# 10w_CREE_LED_driver.net
KiCad netlist of a schematic drawn in EAGLE
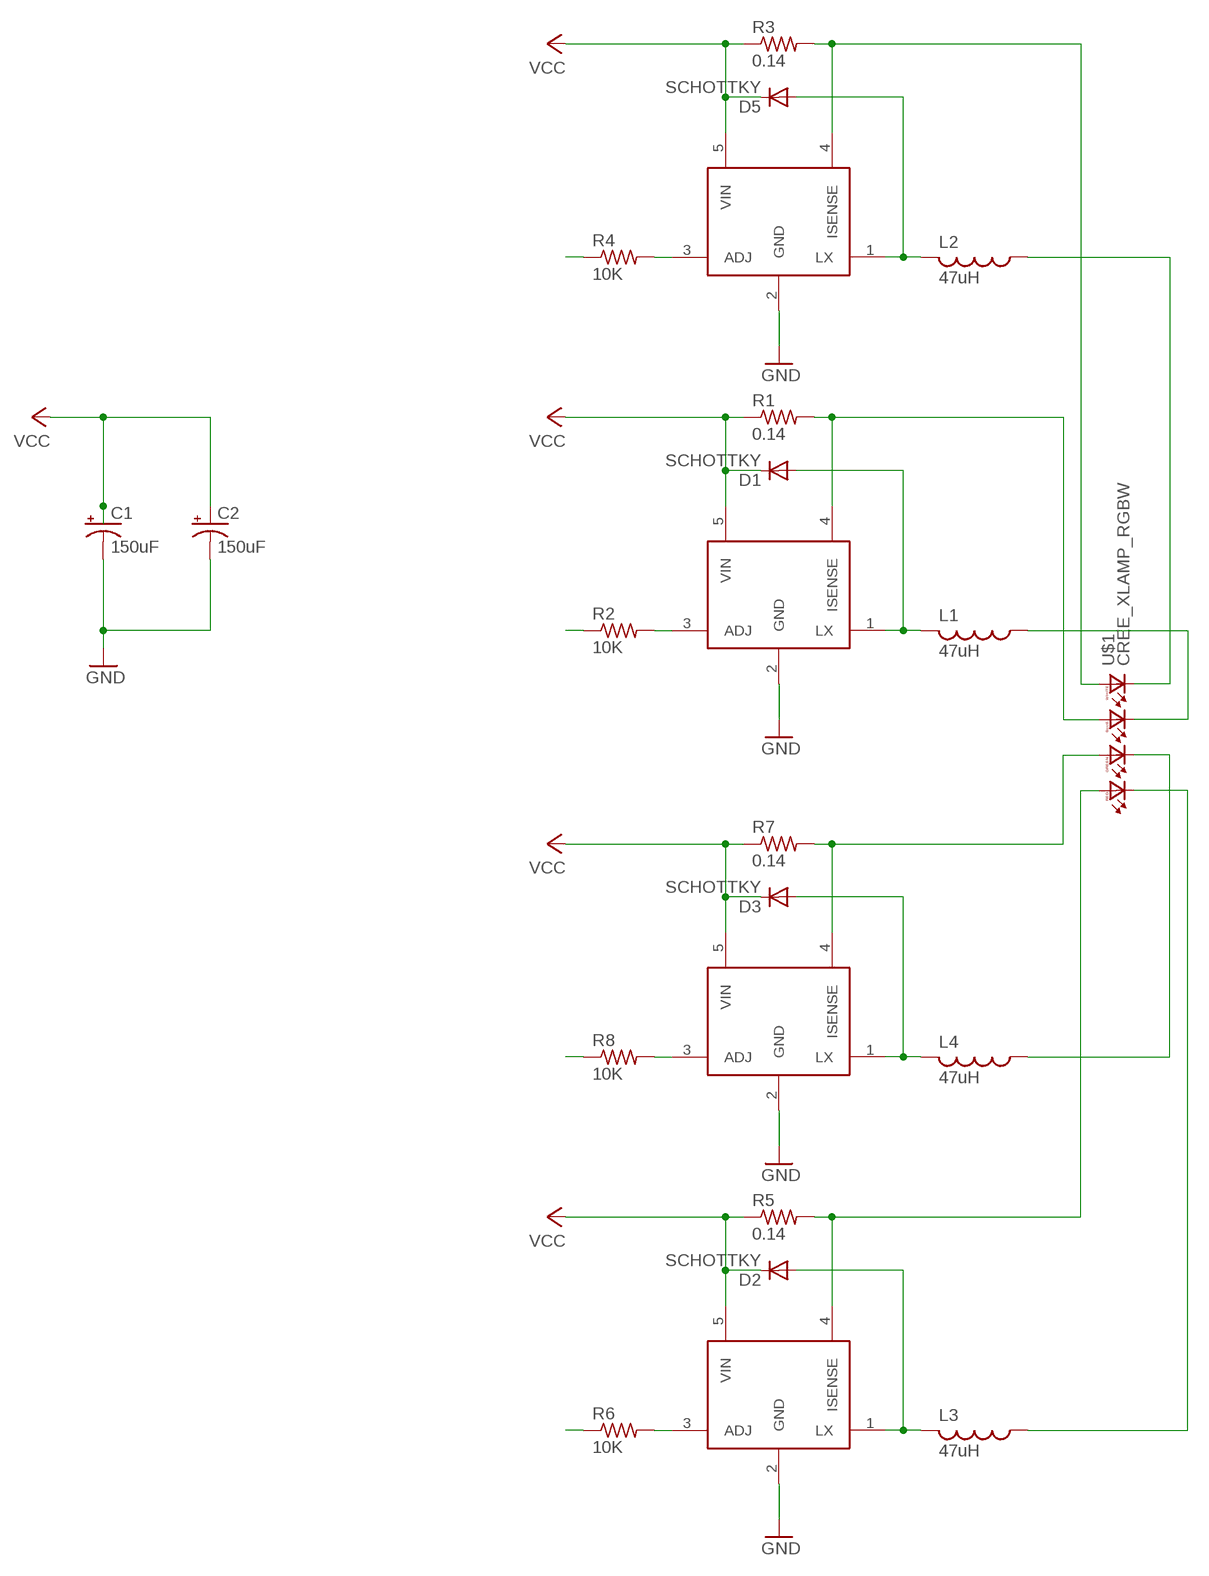
[diagram p0: schematic, sheet 1]

(export (version "E")
  (design (tool "Eeschema 10.0.6"))
  (components
    (comp (ref "C1")
      (value "150uF")
      (footprint "eagle-import:175TMP-0810")
      (libsource (lib "eagle-import") (part "CPOL-US175TMP-0810"))
    )
    (comp (ref "C2")
      (value "150uF")
      (footprint "eagle-import:175TMP-0810")
      (libsource (lib "eagle-import") (part "CPOL-US175TMP-0810"))
    )
    (comp (ref "D1")
      (value "SCHOTTKY")
      (footprint "eagle-import:DO214AC")
      (libsource (lib "eagle-import") (part "DIODE-DO214AC"))
    )
    (comp (ref "D2")
      (value "SCHOTTKY")
      (footprint "eagle-import:DO214AC")
      (libsource (lib "eagle-import") (part "DIODE-DO214AC"))
    )
    (comp (ref "D3")
      (value "SCHOTTKY")
      (footprint "eagle-import:DO214AC")
      (libsource (lib "eagle-import") (part "DIODE-DO214AC"))
    )
    (comp (ref "D5")
      (value "SCHOTTKY")
      (footprint "eagle-import:DO214AC")
      (libsource (lib "eagle-import") (part "DIODE-DO214AC"))
    )
    (comp (ref "L1")
      (value "47uH")
      (footprint "eagle-import:TDK6045")
      (libsource (lib "eagle-import") (part "L-US"))
    )
    (comp (ref "L2")
      (value "47uH")
      (footprint "eagle-import:TDK6045")
      (libsource (lib "eagle-import") (part "L-US"))
    )
    (comp (ref "L3")
      (value "47uH")
      (footprint "eagle-import:TDK6045")
      (libsource (lib "eagle-import") (part "L-US"))
    )
    (comp (ref "L4")
      (value "47uH")
      (footprint "eagle-import:TDK6045")
      (libsource (lib "eagle-import") (part "L-US"))
    )
    (comp (ref "R1")
      (value "0.14")
      (footprint "eagle-import:R0805")
      (libsource (lib "eagle-import") (part "R-US_R0805"))
    )
    (comp (ref "R2")
      (value "10K")
      (footprint "eagle-import:R0603")
      (libsource (lib "eagle-import") (part "R-US_R0603"))
    )
    (comp (ref "R3")
      (value "0.14")
      (footprint "eagle-import:R0805")
      (libsource (lib "eagle-import") (part "R-US_R0805"))
    )
    (comp (ref "R4")
      (value "10K")
      (footprint "eagle-import:R0603")
      (libsource (lib "eagle-import") (part "R-US_R0603"))
    )
    (comp (ref "R5")
      (value "0.14")
      (footprint "eagle-import:R0805")
      (libsource (lib "eagle-import") (part "R-US_R0805"))
    )
    (comp (ref "R6")
      (value "10K")
      (footprint "eagle-import:R0603")
      (libsource (lib "eagle-import") (part "R-US_R0603"))
    )
    (comp (ref "R7")
      (value "0.14")
      (footprint "eagle-import:R0805")
      (libsource (lib "eagle-import") (part "R-US_R0805"))
    )
    (comp (ref "R8")
      (value "10K")
      (footprint "eagle-import:R0603")
      (libsource (lib "eagle-import") (part "R-US_R0603"))
    )
    (comp (ref "U$1")
      (value "CREE_XLAMP_RGBW")
      (footprint "eagle-import:CREE_XLAMP_XML")
      (libsource (lib "eagle-import") (part "CREE_XLAMP_RGBW"))
    )
    (comp (ref "U$2")
      (value "ZLED7000-LEDDRIVER")
      (footprint "eagle-import:SOT89-5")
      (libsource (lib "eagle-import") (part "ZLED7000-LEDDRIVER"))
    )
    (comp (ref "U$3")
      (value "ZLED7000-LEDDRIVER")
      (footprint "eagle-import:SOT89-5")
      (libsource (lib "eagle-import") (part "ZLED7000-LEDDRIVER"))
    )
    (comp (ref "U$4")
      (value "ZLED7000-LEDDRIVER")
      (footprint "eagle-import:SOT89-5")
      (libsource (lib "eagle-import") (part "ZLED7000-LEDDRIVER"))
    )
    (comp (ref "U$6")
      (value "ZLED7000-LEDDRIVER")
      (footprint "eagle-import:SOT89-5")
      (libsource (lib "eagle-import") (part "ZLED7000-LEDDRIVER"))
    )
  )
  (nets
    (net (code "1") (name "GND") (class "Default")
      (node (ref "C1") (pin "-") (pinfunction "-_-") (pintype "passive"))
      (node (ref "C2") (pin "-") (pinfunction "-_-") (pintype "passive"))
      (node (ref "U$2") (pin "2") (pinfunction "GND_2") (pintype "bidirectional"))
      (node (ref "U$3") (pin "2") (pinfunction "GND_2") (pintype "bidirectional"))
      (node (ref "U$4") (pin "2") (pinfunction "GND_2") (pintype "bidirectional"))
      (node (ref "U$6") (pin "2") (pinfunction "GND_2") (pintype "bidirectional"))
    )
    (net (code "2") (name "Net-(U$1-BA)") (class "Default")
      (node (ref "R1") (pin "2") (pinfunction "2_2") (pintype "passive"))
      (node (ref "U$1") (pin "3") (pinfunction "BA_3") (pintype "passive"))
      (node (ref "U$2") (pin "4") (pinfunction "ISENSE_4") (pintype "bidirectional"))
    )
    (net (code "3") (name "Net-(U$1-BC)") (class "Default")
      (node (ref "L1") (pin "1") (pinfunction "1_1") (pintype "passive"))
      (node (ref "U$1") (pin "6") (pinfunction "BC_6") (pintype "passive"))
    )
    (net (code "4") (name "Net-(U$1-GA)") (class "Default")
      (node (ref "R7") (pin "2") (pinfunction "2_2") (pintype "passive"))
      (node (ref "U$1") (pin "2") (pinfunction "GA_2") (pintype "passive"))
      (node (ref "U$4") (pin "4") (pinfunction "ISENSE_4") (pintype "bidirectional"))
    )
    (net (code "5") (name "Net-(U$1-GC)") (class "Default")
      (node (ref "L4") (pin "1") (pinfunction "1_1") (pintype "passive"))
      (node (ref "U$1") (pin "7") (pinfunction "GC_7") (pintype "passive"))
    )
    (net (code "6") (name "Net-(U$1-RA)") (class "Default")
      (node (ref "R5") (pin "2") (pinfunction "2_2") (pintype "passive"))
      (node (ref "U$1") (pin "1") (pinfunction "RA_1") (pintype "passive"))
      (node (ref "U$3") (pin "4") (pinfunction "ISENSE_4") (pintype "bidirectional"))
    )
    (net (code "7") (name "Net-(U$1-RC)") (class "Default")
      (node (ref "L3") (pin "1") (pinfunction "1_1") (pintype "passive"))
      (node (ref "U$1") (pin "8") (pinfunction "RC_8") (pintype "passive"))
    )
    (net (code "8") (name "Net-(U$1-WA)") (class "Default")
      (node (ref "R3") (pin "2") (pinfunction "2_2") (pintype "passive"))
      (node (ref "U$1") (pin "4") (pinfunction "WA_4") (pintype "passive"))
      (node (ref "U$6") (pin "4") (pinfunction "ISENSE_4") (pintype "bidirectional"))
    )
    (net (code "9") (name "Net-(U$1-WC)") (class "Default")
      (node (ref "L2") (pin "1") (pinfunction "1_1") (pintype "passive"))
      (node (ref "U$1") (pin "5") (pinfunction "WC_5") (pintype "passive"))
    )
    (net (code "10") (name "Net-(U$2-ADJ)") (class "Default")
      (node (ref "R2") (pin "2") (pinfunction "2_2") (pintype "passive"))
      (node (ref "U$2") (pin "3") (pinfunction "ADJ_3") (pintype "bidirectional"))
    )
    (net (code "11") (name "Net-(U$2-LX)") (class "Default")
      (node (ref "D1") (pin "A") (pinfunction "A_A") (pintype "passive"))
      (node (ref "L1") (pin "2") (pinfunction "2_2") (pintype "passive"))
      (node (ref "U$2") (pin "1") (pinfunction "LX_1") (pintype "bidirectional"))
    )
    (net (code "12") (name "Net-(U$3-ADJ)") (class "Default")
      (node (ref "R6") (pin "2") (pinfunction "2_2") (pintype "passive"))
      (node (ref "U$3") (pin "3") (pinfunction "ADJ_3") (pintype "bidirectional"))
    )
    (net (code "13") (name "Net-(U$3-LX)") (class "Default")
      (node (ref "D2") (pin "A") (pinfunction "A_A") (pintype "passive"))
      (node (ref "L3") (pin "2") (pinfunction "2_2") (pintype "passive"))
      (node (ref "U$3") (pin "1") (pinfunction "LX_1") (pintype "bidirectional"))
    )
    (net (code "14") (name "Net-(U$4-ADJ)") (class "Default")
      (node (ref "R8") (pin "2") (pinfunction "2_2") (pintype "passive"))
      (node (ref "U$4") (pin "3") (pinfunction "ADJ_3") (pintype "bidirectional"))
    )
    (net (code "15") (name "Net-(U$4-LX)") (class "Default")
      (node (ref "D3") (pin "A") (pinfunction "A_A") (pintype "passive"))
      (node (ref "L4") (pin "2") (pinfunction "2_2") (pintype "passive"))
      (node (ref "U$4") (pin "1") (pinfunction "LX_1") (pintype "bidirectional"))
    )
    (net (code "16") (name "Net-(U$6-ADJ)") (class "Default")
      (node (ref "R4") (pin "2") (pinfunction "2_2") (pintype "passive"))
      (node (ref "U$6") (pin "3") (pinfunction "ADJ_3") (pintype "bidirectional"))
    )
    (net (code "17") (name "Net-(U$6-LX)") (class "Default")
      (node (ref "D5") (pin "A") (pinfunction "A_A") (pintype "passive"))
      (node (ref "L2") (pin "2") (pinfunction "2_2") (pintype "passive"))
      (node (ref "U$6") (pin "1") (pinfunction "LX_1") (pintype "bidirectional"))
    )
    (net (code "18") (name "VCC") (class "Default")
      (node (ref "C1") (pin "+") (pinfunction "+_+") (pintype "passive"))
      (node (ref "C2") (pin "+") (pinfunction "+_+") (pintype "passive"))
      (node (ref "D1") (pin "C") (pinfunction "C_C") (pintype "passive"))
      (node (ref "D2") (pin "C") (pinfunction "C_C") (pintype "passive"))
      (node (ref "D3") (pin "C") (pinfunction "C_C") (pintype "passive"))
      (node (ref "D5") (pin "C") (pinfunction "C_C") (pintype "passive"))
      (node (ref "R1") (pin "1") (pinfunction "1_1") (pintype "passive"))
      (node (ref "R3") (pin "1") (pinfunction "1_1") (pintype "passive"))
      (node (ref "R5") (pin "1") (pinfunction "1_1") (pintype "passive"))
      (node (ref "R7") (pin "1") (pinfunction "1_1") (pintype "passive"))
      (node (ref "U$2") (pin "5") (pinfunction "VIN_5") (pintype "bidirectional"))
      (node (ref "U$3") (pin "5") (pinfunction "VIN_5") (pintype "bidirectional"))
      (node (ref "U$4") (pin "5") (pinfunction "VIN_5") (pintype "bidirectional"))
      (node (ref "U$6") (pin "5") (pinfunction "VIN_5") (pintype "bidirectional"))
    )
    (net (code "19") (name "unconnected-(R2-Pad1)") (class "Default")
      (node (ref "R2") (pin "1") (pinfunction "1_1") (pintype "passive"))
    )
    (net (code "20") (name "unconnected-(R4-Pad1)") (class "Default")
      (node (ref "R4") (pin "1") (pinfunction "1_1") (pintype "passive"))
    )
    (net (code "21") (name "unconnected-(R6-Pad1)") (class "Default")
      (node (ref "R6") (pin "1") (pinfunction "1_1") (pintype "passive"))
    )
    (net (code "22") (name "unconnected-(R8-Pad1)") (class "Default")
      (node (ref "R8") (pin "1") (pinfunction "1_1") (pintype "passive"))
    )
  )
)
